# 06_-_IO_Ports.net
KiCad netlist of a schematic drawn in Altium Designer
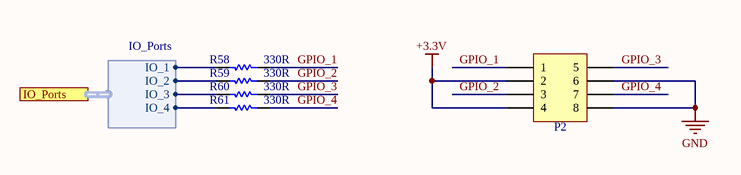
[diagram p0: [06] - IO_Ports.SchDoc]

(export (version "E")
  (design (tool "Eeschema 10.0.6"))
  (components
    (comp (ref "P2")
      (value "Header 4X2A")
      (footprint "Blue Tractor-2021:CON: PLD-2*4")
      (description "Header, 4-Pin, Dual row")
      (fields (field (name "PUBLISHER") "Altium Limited"))
      (libsource (lib "Miscellaneous Connectors") (part "Header 4X2A"))
    )
    (comp (ref "R58")
      (value "Res1")
      (footprint "Blue Tractor-2021:0603_R")
      (description "Chip Resistor")
      (fields
        (field (name "MANUFACTURER") "Panasonic")
        (field (name "MANUFACTURER PART NUMBER") "ERJ-3EKF3300V")
        (field (name "RESISTANCE") "330R")
      )
      (libsource (lib "Altium_Library") (part "Res1"))
    )
    (comp (ref "R59")
      (value "Res1")
      (footprint "Blue Tractor-2021:0603_R")
      (description "Chip Resistor")
      (fields
        (field (name "MANUFACTURER") "Panasonic")
        (field (name "MANUFACTURER PART NUMBER") "ERJ-3EKF3300V")
        (field (name "RESISTANCE") "330R")
      )
      (libsource (lib "Altium_Library") (part "Res1"))
    )
    (comp (ref "R60")
      (value "Res1")
      (footprint "Blue Tractor-2021:0603_R")
      (description "Chip Resistor")
      (fields
        (field (name "MANUFACTURER") "Panasonic")
        (field (name "MANUFACTURER PART NUMBER") "ERJ-3EKF3300V")
        (field (name "RESISTANCE") "330R")
      )
      (libsource (lib "Altium_Library") (part "Res1"))
    )
    (comp (ref "R61")
      (value "Res1")
      (footprint "Blue Tractor-2021:0603_R")
      (description "Chip Resistor")
      (fields
        (field (name "MANUFACTURER") "Panasonic")
        (field (name "MANUFACTURER PART NUMBER") "ERJ-3EKF3300V")
        (field (name "RESISTANCE") "330R")
      )
      (libsource (lib "Altium_Library") (part "Res1"))
    )
  )
  (nets
    (net (code "2") (name "+3.3V") (class "Default")
      (node (ref "P2") (pin "2") (pinfunction "2_2") (pintype "passive"))
      (node (ref "P2") (pin "4") (pinfunction "4_4") (pintype "passive"))
    )
    (net (code "3") (name "/GPIO_1") (class "Default")
      (node (ref "P2") (pin "1") (pinfunction "1_1") (pintype "passive"))
      (node (ref "R58") (pin "2") (pinfunction "2_2") (pintype "passive"))
    )
    (net (code "4") (name "/GPIO_2") (class "Default")
      (node (ref "P2") (pin "3") (pinfunction "3_3") (pintype "passive"))
      (node (ref "R59") (pin "2") (pinfunction "2_2") (pintype "passive"))
    )
    (net (code "5") (name "/GPIO_3") (class "Default")
      (node (ref "P2") (pin "5") (pinfunction "5_5") (pintype "passive"))
      (node (ref "R60") (pin "2") (pinfunction "2_2") (pintype "passive"))
    )
    (net (code "6") (name "/GPIO_4") (class "Default")
      (node (ref "P2") (pin "7") (pinfunction "7_7") (pintype "passive"))
      (node (ref "R61") (pin "2") (pinfunction "2_2") (pintype "passive"))
    )
    (net (code "7") (name "/IO_1") (class "Default")
      (node (ref "R58") (pin "1") (pinfunction "1_1") (pintype "passive"))
    )
    (net (code "8") (name "/IO_2") (class "Default")
      (node (ref "R59") (pin "1") (pinfunction "1_1") (pintype "passive"))
    )
    (net (code "9") (name "/IO_3") (class "Default")
      (node (ref "R60") (pin "1") (pinfunction "1_1") (pintype "passive"))
    )
    (net (code "10") (name "/IO_4") (class "Default")
      (node (ref "R61") (pin "1") (pinfunction "1_1") (pintype "passive"))
    )
    (net (code "12") (name "GND") (class "Default")
      (node (ref "P2") (pin "6") (pinfunction "6_6") (pintype "passive"))
      (node (ref "P2") (pin "8") (pinfunction "8_8") (pintype "passive"))
    )
  )
)
